# USB_Programmer.net
KiCad netlist of a schematic drawn in Altium Designer
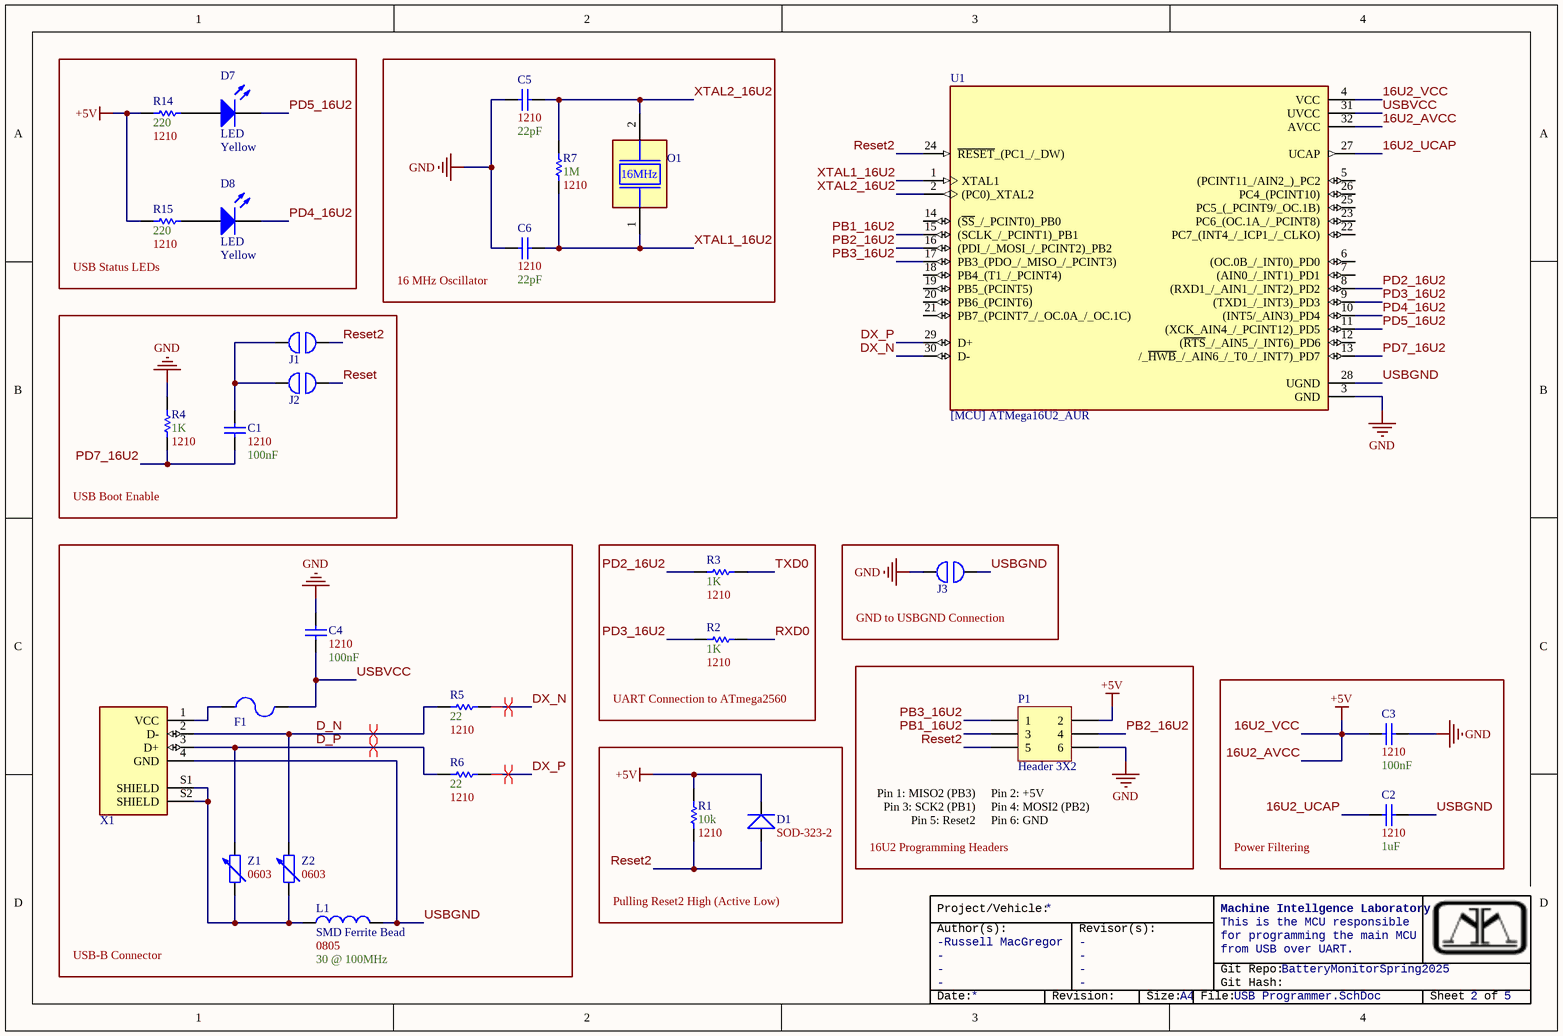
[diagram p0: USB Programmer.SchDoc]

(export (version "E")
  (design (tool "Eeschema 10.0.6"))
  (components
    (comp (ref "C1")
      (value "SMD Cap - Nonpolarized")
      (footprint "SMD Capacitor [1210]")
      (fields
        (field (name "MOUSER PART #") "581-12107C104KAT2A")
        (field (name "SIZE PACKAGE") "1210")
        (field (name "CAPACITANCE") "100nF")
      )
      (libsource (lib "RADM Components") (part "SMD Cap - Nonpolarized"))
    )
    (comp (ref "C2")
      (value "SMD Cap - Nonpolarized")
      (footprint "SMD Capacitor [1210]")
      (fields
        (field (name "MOUSER PART #") "80-C1210X105K5RAUTO")
        (field (name "SIZE PACKAGE") "1210")
        (field (name "CAPACITANCE") "1uF")
      )
      (libsource (lib "RADM Components") (part "SMD Cap - Nonpolarized"))
    )
    (comp (ref "C3")
      (value "SMD Cap - Nonpolarized")
      (footprint "SMD Capacitor [1210]")
      (fields
        (field (name "MOUSER PART #") "581-12107C104KAT2A")
        (field (name "SIZE PACKAGE") "1210")
        (field (name "CAPACITANCE") "100nF")
      )
      (libsource (lib "RADM Components") (part "SMD Cap - Nonpolarized"))
    )
    (comp (ref "C4")
      (value "SMD Cap - Nonpolarized")
      (footprint "SMD Capacitor [1210]")
      (fields
        (field (name "MOUSER PART #") "581-12107C104KAT2A")
        (field (name "SIZE PACKAGE") "1210")
        (field (name "CAPACITANCE") "100nF")
      )
      (libsource (lib "RADM Components") (part "SMD Cap - Nonpolarized"))
    )
    (comp (ref "C5")
      (value "SMD Cap - Nonpolarized")
      (footprint "SMD Capacitor [1210]")
      (fields
        (field (name "MOUSER PART #") "77-VJ1210A220JXGAT5Z")
        (field (name "SIZE PACKAGE") "1210")
        (field (name "CAPACITANCE") "22pF")
      )
      (libsource (lib "RADM Components") (part "SMD Cap - Nonpolarized"))
    )
    (comp (ref "C6")
      (value "SMD Cap - Nonpolarized")
      (footprint "SMD Capacitor [1210]")
      (fields
        (field (name "MOUSER PART #") "77-VJ1210A220JXGAT5Z")
        (field (name "SIZE PACKAGE") "1210")
        (field (name "CAPACITANCE") "22pF")
      )
      (libsource (lib "RADM Components") (part "SMD Cap - Nonpolarized"))
    )
    (comp (ref "D1")
      (value "SMD Diode")
      (footprint "SMD Diode [SOD-323-2]")
      (description "Part #: CD1206-S01575\r\nJLC Part #: C75465")
      (fields (field (name "JLC PART #") "C75465") (field (name "SIZE PACKAGE") "SOD-323-2"))
      (libsource (lib "RADM Components") (part "SMD Diode"))
    )
    (comp (ref "D7")
      (value "LED")
      (footprint "Small Yellow LED")
      (description "3mm LED")
      (fields (field (name "COLOR") "Yellow"))
      (libsource (lib "RADM Components") (part "Small LED"))
    )
    (comp (ref "D8")
      (value "LED")
      (footprint "Small Yellow LED")
      (description "3mm LED")
      (fields (field (name "COLOR") "Yellow"))
      (libsource (lib "RADM Components") (part "Small LED"))
    )
    (comp (ref "F1")
      (value "SMD 500mA Resetable Fuse")
      (footprint "SMD 500mA Resetable Fuse")
      (description "Part #: MF-MSMF050-2\r\nJLC Part #: C17313")
      (fields (field (name "JLC PART #") "C17313"))
      (libsource (lib "RADM Components") (part "SMD 500mA Resetable Fuse"))
    )
    (comp (ref "J1")
      (value "Solderable Jumper")
      (footprint "Solderable Jumper")
      (description "Solderable jumper")
      (libsource (lib "RADM Components") (part "Solderable Jumper"))
    )
    (comp (ref "J2")
      (value "Solderable Jumper")
      (footprint "Solderable Jumper")
      (description "Solderable jumper")
      (libsource (lib "RADM Components") (part "Solderable Jumper"))
    )
    (comp (ref "J3")
      (value "Solderable Jumper")
      (footprint "Solderable Jumper")
      (description "Solderable jumper")
      (libsource (lib "RADM Components") (part "Solderable Jumper"))
    )
    (comp (ref "L1")
      (value "SMD Ferrite Bead")
      (footprint "SMD Ferrite Bead [0805]")
      (description "JLC Part #: C840593 (default)")
      (fields
        (field (name "JLC PART #") "C840593")
        (field (name "SIZE PACKAGE") "0805")
        (field (name "RES @ FREQ") "30 @ 100MHz")
      )
      (libsource (lib "RADM Components") (part "SMD Ferrite Bead"))
    )
    (comp (ref "O1")
      (value "Thru-Hole 16MHz Oscillator")
      (footprint "Thru-Hole 16MHz Oscillator")
      (description "Part #: 2780-HC49US-FF3F18-16.000MHZ-ND (16MHz)\r\nJLC Part #: C6873445")
      (fields (field (name "JLC PART #") "C6873445"))
      (libsource (lib "RADM Components") (part "Thru-Hole 16MHz Oscillator"))
    )
    (comp (ref "P1")
      (value "Header 3X2")
      (footprint "HDR2X3")
      (description "Header, 3-Pin, Dual row")
      (fields (field (name "PUBLISHER") "Altium Limited"))
      (libsource (lib "Miscellaneous Connectors") (part "Header 3X2"))
    )
    (comp (ref "R1")
      (value "SMD Resistor")
      (footprint "SMD Resistor [1210]")
      (description "JLC Part #: C728401\r\n(for 1M Ohm Res)")
      (fields
        (field (name "MOUSER PART #") "71-CRCW121010K0JNAIF")
        (field (name "RESISTANCE") "10k")
        (field (name "SIZE PACKAGE") "1210")
      )
      (libsource (lib "RADM Components") (part "SMD Resistor"))
    )
    (comp (ref "R2")
      (value "SMD Resistor")
      (footprint "SMD Resistor [1210]")
      (fields
        (field (name "MOUSER PART #") "71-CRCW12101K00JNAIF")
        (field (name "RESISTANCE") "1K")
        (field (name "SIZE PACKAGE") "1210")
      )
      (libsource (lib "RADM Components") (part "SMD Resistor"))
    )
    (comp (ref "R3")
      (value "SMD Resistor")
      (footprint "SMD Resistor [1210]")
      (fields
        (field (name "MOUSER PART #") "71-CRCW12101K00JNAIF")
        (field (name "RESISTANCE") "1K")
        (field (name "SIZE PACKAGE") "1210")
      )
      (libsource (lib "RADM Components") (part "SMD Resistor"))
    )
    (comp (ref "R4")
      (value "SMD Resistor")
      (footprint "SMD Resistor [1210]")
      (fields
        (field (name "MOUSER PART #") "71-CRCW12101K00JNAIF")
        (field (name "RESISTANCE") "1K")
        (field (name "SIZE PACKAGE") "1210")
      )
      (libsource (lib "RADM Components") (part "SMD Resistor"))
    )
    (comp (ref "R5")
      (value "SMD Resistor")
      (footprint "SMD Resistor [1210]")
      (fields
        (field (name "MOUSER PART #") "71-CRCW121022R0JNEAH")
        (field (name "RESISTANCE") "22")
        (field (name "SIZE PACKAGE") "1210")
      )
      (libsource (lib "RADM Components") (part "SMD Resistor"))
    )
    (comp (ref "R6")
      (value "SMD Resistor")
      (footprint "SMD Resistor [1210]")
      (fields
        (field (name "MOUSER PART #") "71-CRCW121022R0JNEAH")
        (field (name "RESISTANCE") "22")
        (field (name "SIZE PACKAGE") "1210")
      )
      (libsource (lib "RADM Components") (part "SMD Resistor"))
    )
    (comp (ref "R7")
      (value "SMD Resistor")
      (footprint "SMD Resistor [1210]")
      (description "JLC Part #: C728401\r\n(for 1M Ohm Res)")
      (fields
        (field (name "JLC PART #") "C728401")
        (field (name "MOUSER PART #") "71-CRCW12101M00FKEAH")
        (field (name "RESISTANCE") "1M")
        (field (name "SIZE PACKAGE") "1210")
      )
      (libsource (lib "RADM Components") (part "SMD Resistor"))
    )
    (comp (ref "R14")
      (value "SMD Resistor")
      (footprint "SMD Resistor [1210]")
      (description "JLC Part #: C728401\r\n(for 1M Ohm Res)")
      (fields
        (field (name "MOUSER PART #") "71-CRCW1210220RJNEAH")
        (field (name "RESISTANCE") "220")
        (field (name "SIZE PACKAGE") "1210")
      )
      (libsource (lib "RADM Components") (part "SMD Resistor"))
    )
    (comp (ref "R15")
      (value "SMD Resistor")
      (footprint "SMD Resistor [1210]")
      (description "JLC Part #: C728401\r\n(for 1M Ohm Res)")
      (fields
        (field (name "MOUSER PART #") "71-CRCW1210220RJNEAH")
        (field (name "RESISTANCE") "220")
        (field (name "SIZE PACKAGE") "1210")
      )
      (libsource (lib "RADM Components") (part "SMD Resistor"))
    )
    (comp (ref "U1")
      (value "[MCU] ATMega16U2_AUR")
      (footprint "SMD ATMega16U2_AUR")
      (description "JLC Part #: C507117")
      (fields (field (name "JLC PART #") "C507117"))
      (libsource (lib "RADM Components") (part "[MCU] ATMega16U2_AUR"))
    )
    (comp (ref "X1")
      (value "USB Type-B Female (Thru-Hole)")
      (footprint "USB Type-B Female (Thru-Hole)")
      (description "Part #: USB-B-S-F-B-TH\r\nJLC Part #: C5714571\r\nOUT OF STOCK JLC")
      (fields (field (name "JLC PART #") "C5714571"))
      (libsource (lib "RADM Components") (part "USB Type-B Female (Thru-Hole)"))
    )
    (comp (ref "Z1")
      (value "SMD Varistor")
      (footprint "SMD Varistor [0603]")
      (description "JLC Part #: C840634 (for 0603 size)")
      (fields (field (name "JLC PART #") "C840634") (field (name "SIZE PACKAGE") "0603"))
      (libsource (lib "RADM Components") (part "SMD Varistor"))
    )
    (comp (ref "Z2")
      (value "SMD Varistor")
      (footprint "SMD Varistor [0603]")
      (description "JLC Part #: C840634 (for 0603 size)")
      (fields (field (name "JLC PART #") "C840634") (field (name "SIZE PACKAGE") "0603"))
      (libsource (lib "RADM Components") (part "SMD Varistor"))
    )
  )
  (nets
    (net (code "1") (name "+5V") (class "Default")
      (node (ref "C3") (pin "2") (pinfunction "2_2") (pintype "passive"))
      (node (ref "D1") (pin "C") (pinfunction "C_C") (pintype "power_in"))
      (node (ref "P1") (pin "2") (pinfunction "2_2") (pintype "passive"))
      (node (ref "R1") (pin "2") (pinfunction "2_2") (pintype "passive"))
      (node (ref "R14") (pin "2") (pinfunction "2_2") (pintype "passive"))
      (node (ref "R15") (pin "2") (pinfunction "2_2") (pintype "passive"))
      (node (ref "U1") (pin "32") (pinfunction "AVCC_32") (pintype "power_in"))
      (node (ref "U1") (pin "4") (pinfunction "VCC_4") (pintype "power_in"))
    )
    (net (code "2") (name "/16U2_UCAP") (class "Default")
      (node (ref "C2") (pin "2") (pinfunction "2_2") (pintype "passive"))
      (node (ref "U1") (pin "27") (pinfunction "UCAP_27") (pintype "output"))
    )
    (net (code "3") (name "/DX_N") (class "Default")
      (node (ref "R5") (pin "2") (pinfunction "2_2") (pintype "passive"))
      (node (ref "U1") (pin "30") (pinfunction "D-_30") (pintype "bidirectional"))
    )
    (net (code "4") (name "/DX_P") (class "Default")
      (node (ref "R6") (pin "2") (pinfunction "2_2") (pintype "passive"))
      (node (ref "U1") (pin "29") (pinfunction "D+_29") (pintype "bidirectional"))
    )
    (net (code "5") (name "/D_N") (class "Default")
      (node (ref "R5") (pin "1") (pinfunction "1_1") (pintype "passive"))
      (node (ref "X1") (pin "2") (pinfunction "D-_2") (pintype "bidirectional"))
      (node (ref "Z2") (pin "2") (pinfunction "2_2") (pintype "passive"))
    )
    (net (code "6") (name "/D_P") (class "Default")
      (node (ref "R6") (pin "1") (pinfunction "1_1") (pintype "passive"))
      (node (ref "X1") (pin "3") (pinfunction "D+_3") (pintype "bidirectional"))
      (node (ref "Z1") (pin "2") (pinfunction "2_2") (pintype "passive"))
    )
    (net (code "7") (name "/PB1_16U2") (class "Default")
      (node (ref "P1") (pin "3") (pinfunction "3_3") (pintype "passive"))
      (node (ref "U1") (pin "15") (pinfunction "(SCLK_/_PCINT1)_PB1_15") (pintype "bidirectional"))
    )
    (net (code "8") (name "/PB2_16U2") (class "Default")
      (node (ref "P1") (pin "4") (pinfunction "4_4") (pintype "passive"))
      (node (ref "U1") (pin "16") (pinfunction "(PDI_/_MOSI_/_PCINT2)_PB2_16") (pintype "bidirectional"))
    )
    (net (code "9") (name "/PB3_16U2") (class "Default")
      (node (ref "P1") (pin "1") (pinfunction "1_1") (pintype "passive"))
      (node (ref "U1") (pin "17") (pinfunction "PB3_(PDO_/_MISO_/_PCINT3)_17") (pintype "bidirectional"))
    )
    (net (code "10") (name "/PD2_16U2") (class "Default")
      (node (ref "R3") (pin "2") (pinfunction "2_2") (pintype "passive"))
      (node (ref "U1") (pin "8") (pinfunction "(RXD1_/_AIN1_/_INT2)_PD2_8") (pintype "bidirectional"))
    )
    (net (code "11") (name "/PD3_16U2") (class "Default")
      (node (ref "R2") (pin "2") (pinfunction "2_2") (pintype "passive"))
      (node (ref "U1") (pin "9") (pinfunction "(TXD1_/_INT3)_PD3_9") (pintype "bidirectional"))
    )
    (net (code "12") (name "/PD4_16U2") (class "Default")
      (node (ref "D8") (pin "2") (pinfunction "K_2") (pintype "passive"))
      (node (ref "U1") (pin "10") (pinfunction "(INT5/_AIN3)_PD4_10") (pintype "bidirectional"))
    )
    (net (code "13") (name "/PD5_16U2") (class "Default")
      (node (ref "D7") (pin "2") (pinfunction "K_2") (pintype "passive"))
      (node (ref "U1") (pin "11") (pinfunction "(XCK_AIN4_/_PCINT12)_PD5_11") (pintype "bidirectional"))
    )
    (net (code "14") (name "/PD7_16U2") (class "Default")
      (node (ref "C1") (pin "1") (pinfunction "1_1") (pintype "passive"))
      (node (ref "R4") (pin "1") (pinfunction "1_1") (pintype "passive"))
      (node (ref "U1") (pin "13") (pinfunction "/_~{HWB}_/_AIN6_/_T0_/_INT7)_PD7_13") (pintype "bidirectional"))
    )
    (net (code "15") (name "/RXD0") (class "Default")
      (node (ref "R2") (pin "1") (pinfunction "1_1") (pintype "passive"))
    )
    (net (code "16") (name "/Reset") (class "Default") (node (ref "J2") (pin "2") (pintype "passive")))
    (net (code "17") (name "/Reset2") (class "Default")
      (node (ref "D1") (pin "A") (pinfunction "A_A") (pintype "power_in"))
      (node (ref "J1") (pin "2") (pintype "passive"))
      (node (ref "P1") (pin "5") (pinfunction "5_5") (pintype "passive"))
      (node (ref "R1") (pin "1") (pinfunction "1_1") (pintype "passive"))
      (node (ref "U1") (pin "24") (pinfunction "~{RESET}_(PC1_/_DW)_24") (pintype "input"))
    )
    (net (code "18") (name "/TXD0") (class "Default")
      (node (ref "R3") (pin "1") (pinfunction "1_1") (pintype "passive"))
    )
    (net (code "19") (name "/USBGND") (class "Default")
      (node (ref "C2") (pin "1") (pinfunction "1_1") (pintype "passive"))
      (node (ref "J3") (pin "2") (pintype "passive"))
      (node (ref "L1") (pin "2") (pinfunction "2_2") (pintype "passive"))
      (node (ref "U1") (pin "28") (pinfunction "UGND_28") (pintype "power_in"))
      (node (ref "X1") (pin "4") (pinfunction "GND_4") (pintype "power_in"))
    )
    (net (code "20") (name "/USBVCC") (class "Default")
      (node (ref "C4") (pin "1") (pinfunction "1_1") (pintype "passive"))
      (node (ref "F1") (pin "2") (pinfunction "2_2") (pintype "passive"))
      (node (ref "U1") (pin "31") (pinfunction "UVCC_31") (pintype "power_in"))
    )
    (net (code "21") (name "/XTAL1_16U2") (class "Default")
      (node (ref "C6") (pin "1") (pinfunction "1_1") (pintype "passive"))
      (node (ref "O1") (pin "1") (pinfunction "1_1") (pintype "passive"))
      (node (ref "R7") (pin "1") (pinfunction "1_1") (pintype "passive"))
      (node (ref "U1") (pin "1") (pinfunction "XTAL1_1") (pintype "input"))
    )
    (net (code "22") (name "/XTAL2_16U2") (class "Default")
      (node (ref "C5") (pin "1") (pinfunction "1_1") (pintype "passive"))
      (node (ref "O1") (pin "2") (pinfunction "2_2") (pintype "passive"))
      (node (ref "R7") (pin "2") (pinfunction "2_2") (pintype "passive"))
      (node (ref "U1") (pin "2") (pinfunction "(PC0)_XTAL2_2") (pintype "output"))
    )
    (net (code "23") (name "GND") (class "Default")
      (node (ref "C3") (pin "1") (pinfunction "1_1") (pintype "passive"))
      (node (ref "C4") (pin "2") (pinfunction "2_2") (pintype "passive"))
      (node (ref "C5") (pin "2") (pinfunction "2_2") (pintype "passive"))
      (node (ref "C6") (pin "2") (pinfunction "2_2") (pintype "passive"))
      (node (ref "J3") (pin "1") (pintype "passive"))
      (node (ref "P1") (pin "6") (pinfunction "6_6") (pintype "passive"))
      (node (ref "R4") (pin "2") (pinfunction "2_2") (pintype "passive"))
      (node (ref "U1") (pin "3") (pinfunction "GND_3") (pintype "power_in"))
    )
    (net (code "24") (name "Net-(C1-Pad2)") (class "Default")
      (node (ref "C1") (pin "2") (pinfunction "2_2") (pintype "passive"))
      (node (ref "J1") (pin "1") (pintype "passive"))
      (node (ref "J2") (pin "1") (pintype "passive"))
    )
    (net (code "25") (name "Net-(D7-A)") (class "Default")
      (node (ref "D7") (pin "1") (pinfunction "A_1") (pintype "passive"))
      (node (ref "R14") (pin "1") (pinfunction "1_1") (pintype "passive"))
    )
    (net (code "26") (name "Net-(D8-A)") (class "Default")
      (node (ref "D8") (pin "1") (pinfunction "A_1") (pintype "passive"))
      (node (ref "R15") (pin "1") (pinfunction "1_1") (pintype "passive"))
    )
    (net (code "27") (name "Net-(L1-Pad1)") (class "Default")
      (node (ref "L1") (pin "1") (pinfunction "1_1") (pintype "passive"))
      (node (ref "X1") (pin "S1") (pinfunction "SHIELD_S1") (pintype "passive"))
      (node (ref "X1") (pin "S2") (pinfunction "SHIELD_S2") (pintype "passive"))
      (node (ref "Z1") (pin "1") (pinfunction "1_1") (pintype "passive"))
      (node (ref "Z2") (pin "1") (pinfunction "1_1") (pintype "passive"))
    )
    (net (code "28") (name "Net-(X1-VCC)") (class "Default")
      (node (ref "F1") (pin "1") (pinfunction "1_1") (pintype "passive"))
      (node (ref "X1") (pin "1") (pinfunction "VCC_1") (pintype "power_in"))
    )
    (net (code "29") (name "unconnected-(U1-(AIN0_{slash}_INT1)_PD1-Pad7)") (class "Default")
      (node (ref "U1") (pin "7") (pinfunction "(AIN0_/_INT1)_PD1_7") (pintype "bidirectional"))
    )
    (net (code "30") (name "unconnected-(U1-(OC.0B_{slash}_INT0)_PD0-Pad6)") (class "Default")
      (node (ref "U1") (pin "6") (pinfunction "(OC.0B_/_INT0)_PD0_6") (pintype "bidirectional"))
    )
    (net (code "31") (name "unconnected-(U1-(PCINT11_{slash}AIN2_)_PC2-Pad5)") (class "Default")
      (node (ref "U1") (pin "5") (pinfunction "(PCINT11_/AIN2_)_PC2_5") (pintype "bidirectional"))
    )
    (net (code "32") (name "unconnected-(U1-(~{RTS}_{slash}_AIN5_{slash}_INT6)_PD6-Pad12)") (class "Default")
      (node (ref "U1") (pin "12") (pinfunction "(~{RTS}_/_AIN5_/_INT6)_PD6_12") (pintype "bidirectional"))
    )
    (net (code "33") (name "unconnected-(U1-(~{SS}_{slash}_PCINT0)_PB0-Pad14)") (class "Default")
      (node (ref "U1") (pin "14") (pinfunction "(~{SS}_/_PCINT0)_PB0_14") (pintype "bidirectional"))
    )
    (net (code "34") (name "unconnected-(U1-PB4_(T1_{slash}_PCINT4)-Pad18)") (class "Default")
      (node (ref "U1") (pin "18") (pinfunction "PB4_(T1_/_PCINT4)_18") (pintype "bidirectional"))
    )
    (net (code "35") (name "unconnected-(U1-PB5_(PCINT5)-Pad19)") (class "Default")
      (node (ref "U1") (pin "19") (pinfunction "PB5_(PCINT5)_19") (pintype "bidirectional"))
    )
    (net (code "36") (name "unconnected-(U1-PB6_(PCINT6)-Pad20)") (class "Default")
      (node (ref "U1") (pin "20") (pinfunction "PB6_(PCINT6)_20") (pintype "bidirectional"))
    )
    (net (code "37") (name "unconnected-(U1-PB7_(PCINT7_{slash}_OC.0A_{slash}_OC.1C)-Pad21)") (class "Default")
      (node (ref "U1") (pin "21") (pinfunction "PB7_(PCINT7_/_OC.0A_/_OC.1C)_21") (pintype "bidirectional"))
    )
    (net (code "38") (name "unconnected-(U1-PC4_(PCINT10)-Pad26)") (class "Default")
      (node (ref "U1") (pin "26") (pinfunction "PC4_(PCINT10)_26") (pintype "bidirectional"))
    )
    (net (code "39") (name "unconnected-(U1-PC5_(_PCINT9{slash}_OC.1B)-Pad25)") (class "Default")
      (node (ref "U1") (pin "25") (pinfunction "PC5_(_PCINT9/_OC.1B)_25") (pintype "bidirectional"))
    )
    (net (code "40") (name "unconnected-(U1-PC6_(OC.1A_{slash}_PCINT8)-Pad23)") (class "Default")
      (node (ref "U1") (pin "23") (pinfunction "PC6_(OC.1A_/_PCINT8)_23") (pintype "bidirectional"))
    )
    (net (code "41") (name "unconnected-(U1-PC7_(INT4_{slash}_ICP1_{slash}_CLKO)-Pad22)") (class "Default")
      (node (ref "U1") (pin "22") (pinfunction "PC7_(INT4_/_ICP1_/_CLKO)_22") (pintype "bidirectional"))
    )
  )
)
